# Arduino-DUE-V03A.net
KiCad netlist of a schematic drawn in EAGLE
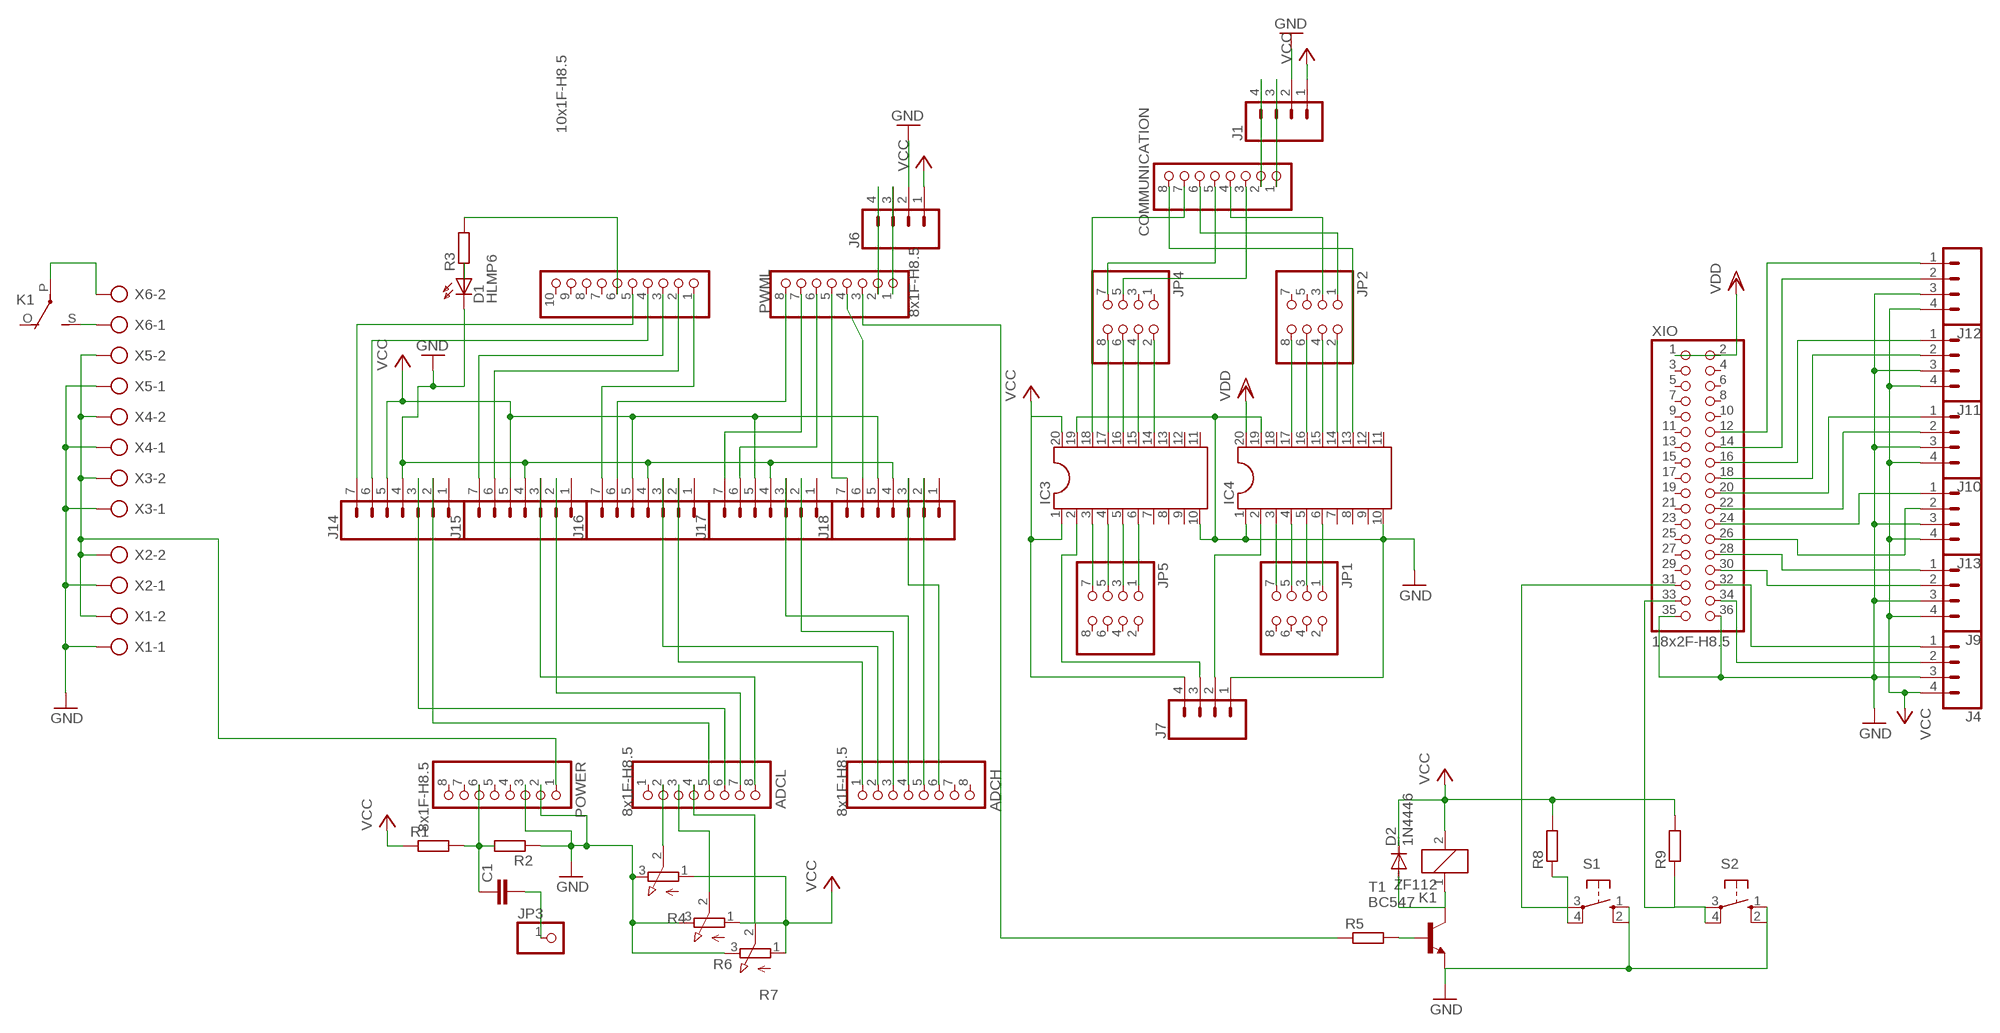
[diagram p0: schematic, sheet 1]

(export (version "E")
  (design (tool "Eeschema 10.0.6"))
  (components
    (comp (ref "ADCH")
      (value "8x1F-H8.5")
      (footprint "eagle-import:1X08")
      (libsource (lib "eagle-import") (part "PINHD-1X8"))
    )
    (comp (ref "ADCL")
      (value "8x1F-H8.5")
      (footprint "eagle-import:1X08")
      (libsource (lib "eagle-import") (part "PINHD-1X8"))
    )
    (comp (ref "C1")
      (value "C-EU025-025X050")
      (footprint "eagle-import:C025-025X050")
      (libsource (lib "eagle-import") (part "C-EU025-025X050"))
    )
    (comp (ref "COMMUNICATION")
      (value "8x1F-H8.5")
      (footprint "eagle-import:1X08")
      (libsource (lib "eagle-import") (part "PINHD-1X8"))
    )
    (comp (ref "D1")
      (value "HLMP6")
      (footprint "eagle-import:HLMP6")
      (fields (field (name "MF") "AGILENT TECHNOLOGIES") (field (name "MPN") "HLMP-6500"))
      (libsource (lib "eagle-import") (part "HLMP6"))
    )
    (comp (ref "D2")
      (value "1N4446")
      (footprint "eagle-import:DO35-10")
      (libsource (lib "eagle-import") (part "1N4446"))
    )
    (comp (ref "IC3")
      (value "DIL20S")
      (footprint "eagle-import:SOCKET-20")
      (libsource (lib "eagle-import") (part "DIL20S"))
    )
    (comp (ref "IC4")
      (value "DIL20S")
      (footprint "eagle-import:SOCKET-20")
      (libsource (lib "eagle-import") (part "DIL20S"))
    )
    (comp (ref "J1")
      (value "CONN_04LONGPADS")
      (footprint "eagle-import:1X04_LONGPADS")
      (libsource (lib "eagle-import") (part "CONN_04LONGPADS"))
    )
    (comp (ref "J4")
      (value "CONN_04LONGPADS")
      (footprint "eagle-import:1X04_LONGPADS")
      (libsource (lib "eagle-import") (part "CONN_04LONGPADS"))
    )
    (comp (ref "J6")
      (value "CONN_04LONGPADS")
      (footprint "eagle-import:1X04_LONGPADS")
      (libsource (lib "eagle-import") (part "CONN_04LONGPADS"))
    )
    (comp (ref "J7")
      (value "CONN_04LONGPADS")
      (footprint "eagle-import:1X04_LONGPADS")
      (libsource (lib "eagle-import") (part "CONN_04LONGPADS"))
    )
    (comp (ref "J9")
      (value "CONN_04LONGPADS")
      (footprint "eagle-import:1X04_LONGPADS")
      (libsource (lib "eagle-import") (part "CONN_04LONGPADS"))
    )
    (comp (ref "J10")
      (value "CONN_04LONGPADS")
      (footprint "eagle-import:1X04_LONGPADS")
      (libsource (lib "eagle-import") (part "CONN_04LONGPADS"))
    )
    (comp (ref "J11")
      (value "CONN_04LONGPADS")
      (footprint "eagle-import:1X04_LONGPADS")
      (libsource (lib "eagle-import") (part "CONN_04LONGPADS"))
    )
    (comp (ref "J12")
      (value "CONN_04LONGPADS")
      (footprint "eagle-import:1X04_LONGPADS")
      (libsource (lib "eagle-import") (part "CONN_04LONGPADS"))
    )
    (comp (ref "J13")
      (value "CONN_04LONGPADS")
      (footprint "eagle-import:1X04_LONGPADS")
      (libsource (lib "eagle-import") (part "CONN_04LONGPADS"))
    )
    (comp (ref "J14")
      (value "CONN_07LONGPADS")
      (footprint "eagle-import:1X07_LONGPADS")
      (libsource (lib "eagle-import") (part "CONN_07LONGPADS"))
    )
    (comp (ref "J15")
      (value "CONN_07LONGPADS")
      (footprint "eagle-import:1X07_LONGPADS")
      (libsource (lib "eagle-import") (part "CONN_07LONGPADS"))
    )
    (comp (ref "J16")
      (value "CONN_07LONGPADS")
      (footprint "eagle-import:1X07_LONGPADS")
      (libsource (lib "eagle-import") (part "CONN_07LONGPADS"))
    )
    (comp (ref "J17")
      (value "CONN_07LONGPADS")
      (footprint "eagle-import:1X07_LONGPADS")
      (libsource (lib "eagle-import") (part "CONN_07LONGPADS"))
    )
    (comp (ref "J18")
      (value "CONN_07LONGPADS")
      (footprint "eagle-import:1X07_LONGPADS")
      (libsource (lib "eagle-import") (part "CONN_07LONGPADS"))
    )
    (comp (ref "JP1")
      (value "PINHD-2X4")
      (footprint "eagle-import:2X04")
      (libsource (lib "eagle-import") (part "PINHD-2X4"))
    )
    (comp (ref "JP2")
      (value "PINHD-2X4")
      (footprint "eagle-import:2X04")
      (libsource (lib "eagle-import") (part "PINHD-2X4"))
    )
    (comp (ref "JP3")
      (value "PINHD-1X1")
      (footprint "eagle-import:1X01")
      (libsource (lib "eagle-import") (part "PINHD-1X1"))
    )
    (comp (ref "JP4")
      (value "PINHD-2X4")
      (footprint "eagle-import:2X04")
      (libsource (lib "eagle-import") (part "PINHD-2X4"))
    )
    (comp (ref "JP5")
      (value "PINHD-2X4")
      (footprint "eagle-import:2X04")
      (libsource (lib "eagle-import") (part "PINHD-2X4"))
    )
    (comp (ref "K1")
      (value "ZF112")
      (footprint "eagle-import:ZF112")
      (libsource (lib "eagle-import") (part "ZF112"))
    )
    (comp (ref "POWER")
      (value "8x1F-H8.5")
      (footprint "eagle-import:1X08")
      (libsource (lib "eagle-import") (part "PINHD-1X8"))
    )
    (comp (ref "PWMH")
      (value "10x1F-H8.5")
      (footprint "eagle-import:1X10")
      (libsource (lib "eagle-import") (part "PINHD-1X10"))
    )
    (comp (ref "PWML")
      (value "8x1F-H8.5")
      (footprint "eagle-import:1X08")
      (libsource (lib "eagle-import") (part "PINHD-1X8"))
    )
    (comp (ref "R1")
      (value "R-EU_0204/7")
      (footprint "eagle-import:0204_7")
      (libsource (lib "eagle-import") (part "R-EU_0204/7"))
    )
    (comp (ref "R2")
      (value "R-EU_0204/7")
      (footprint "eagle-import:0204_7")
      (libsource (lib "eagle-import") (part "R-EU_0204/7"))
    )
    (comp (ref "R3")
      (value "R-EU_0204/7")
      (footprint "eagle-import:0204_7")
      (libsource (lib "eagle-import") (part "R-EU_0204/7"))
    )
    (comp (ref "R4")
      (value "3RP/1610N")
      (footprint "eagle-import:3RP_1610N")
      (libsource (lib "eagle-import") (part "3RP/1610N"))
    )
    (comp (ref "R5")
      (value "R-EU_0204/7")
      (footprint "eagle-import:0204_7")
      (libsource (lib "eagle-import") (part "R-EU_0204/7"))
    )
    (comp (ref "R6")
      (value "3RP/1610N")
      (footprint "eagle-import:3RP_1610N")
      (libsource (lib "eagle-import") (part "3RP/1610N"))
    )
    (comp (ref "R7")
      (value "3RP/1610N")
      (footprint "eagle-import:3RP_1610N")
      (libsource (lib "eagle-import") (part "3RP/1610N"))
    )
    (comp (ref "R8")
      (value "R-EU_0204/7")
      (footprint "eagle-import:0204_7")
      (libsource (lib "eagle-import") (part "R-EU_0204/7"))
    )
    (comp (ref "R9")
      (value "R-EU_0204/7")
      (footprint "eagle-import:0204_7")
      (libsource (lib "eagle-import") (part "R-EU_0204/7"))
    )
    (comp (ref "S1")
      (value "10-XX")
      (footprint "eagle-import:B3F-10XX")
      (fields (field (name "MPN") "B3F-1000"))
      (libsource (lib "eagle-import") (part "10-XX"))
    )
    (comp (ref "S2")
      (value "10-XX")
      (footprint "eagle-import:B3F-10XX")
      (fields (field (name "MPN") "B3F-1000"))
      (libsource (lib "eagle-import") (part "10-XX"))
    )
    (comp (ref "T1")
      (value "BC547")
      (footprint "eagle-import:TO92")
      (libsource (lib "eagle-import") (part "BC547"))
    )
    (comp (ref "X1")
      (value "AK500/2")
      (footprint "eagle-import:AK500_2")
      (libsource (lib "eagle-import") (part "AK500/2"))
    )
    (comp (ref "X2")
      (value "AK500/2")
      (footprint "eagle-import:AK500_2")
      (libsource (lib "eagle-import") (part "AK500/2"))
    )
    (comp (ref "X3")
      (value "AK500/2")
      (footprint "eagle-import:AK500_2")
      (libsource (lib "eagle-import") (part "AK500/2"))
    )
    (comp (ref "X4")
      (value "AK500/2")
      (footprint "eagle-import:AK500_2")
      (libsource (lib "eagle-import") (part "AK500/2"))
    )
    (comp (ref "X5")
      (value "AK500/2")
      (footprint "eagle-import:AK500_2")
      (libsource (lib "eagle-import") (part "AK500/2"))
    )
    (comp (ref "X6")
      (value "AK500/2")
      (footprint "eagle-import:AK500_2")
      (libsource (lib "eagle-import") (part "AK500/2"))
    )
    (comp (ref "XIO")
      (value "18x2F-H8.5")
      (footprint "eagle-import:2X18")
      (libsource (lib "eagle-import") (part "PINHD-2X18"))
    )
  )
  (nets
    (net (code "1") (name "GND") (class "Default")
      (node (ref "D1") (pin "K") (pinfunction "K_K") (pintype "passive"))
      (node (ref "IC3") (pin "10") (pinfunction "10_10") (pintype "passive"))
      (node (ref "IC3") (pin "19") (pinfunction "19_19") (pintype "passive"))
      (node (ref "IC4") (pin "1") (pinfunction "1_1") (pintype "passive"))
      (node (ref "IC4") (pin "10") (pinfunction "10_10") (pintype "passive"))
      (node (ref "IC4") (pin "19") (pinfunction "19_19") (pintype "passive"))
      (node (ref "J1") (pin "2") (pinfunction "2_2") (pintype "passive"))
      (node (ref "J10") (pin "3") (pinfunction "3_3") (pintype "passive"))
      (node (ref "J11") (pin "3") (pinfunction "3_3") (pintype "passive"))
      (node (ref "J12") (pin "3") (pinfunction "3_3") (pintype "passive"))
      (node (ref "J13") (pin "1") (pinfunction "1_1") (pintype "passive"))
      (node (ref "J13") (pin "3") (pinfunction "3_3") (pintype "passive"))
      (node (ref "J14") (pin "4") (pinfunction "4_4") (pintype "passive"))
      (node (ref "J15") (pin "4") (pinfunction "4_4") (pintype "passive"))
      (node (ref "J16") (pin "4") (pinfunction "4_4") (pintype "passive"))
      (node (ref "J17") (pin "4") (pinfunction "4_4") (pintype "passive"))
      (node (ref "J18") (pin "4") (pinfunction "4_4") (pintype "passive"))
      (node (ref "J4") (pin "3") (pinfunction "3_3") (pintype "passive"))
      (node (ref "J6") (pin "2") (pinfunction "2_2") (pintype "passive"))
      (node (ref "J7") (pin "1") (pinfunction "1_1") (pintype "passive"))
      (node (ref "J9") (pin "3") (pinfunction "3_3") (pintype "passive"))
      (node (ref "POWER") (pin "2") (pinfunction "2_2") (pintype "passive"))
      (node (ref "POWER") (pin "3") (pinfunction "3_3") (pintype "passive"))
      (node (ref "R2") (pin "1") (pinfunction "1_1") (pintype "passive"))
      (node (ref "R4") (pin "3") (pinfunction "E_3") (pintype "passive"))
      (node (ref "R6") (pin "3") (pinfunction "E_3") (pintype "passive"))
      (node (ref "R7") (pin "3") (pinfunction "E_3") (pintype "passive"))
      (node (ref "S1") (pin "1") (pinfunction "S_1") (pintype "passive"))
      (node (ref "S1") (pin "2") (pinfunction "S1_2") (pintype "passive"))
      (node (ref "S2") (pin "1") (pinfunction "S_1") (pintype "passive"))
      (node (ref "S2") (pin "2") (pinfunction "S1_2") (pintype "passive"))
      (node (ref "T1") (pin "1") (pinfunction "E_1") (pintype "passive"))
      (node (ref "X1") (pin "1") (pinfunction "KL_1") (pintype "passive"))
      (node (ref "X2") (pin "1") (pinfunction "KL_1") (pintype "passive"))
      (node (ref "X3") (pin "1") (pinfunction "KL_1") (pintype "passive"))
      (node (ref "X4") (pin "1") (pinfunction "KL_1") (pintype "passive"))
      (node (ref "X5") (pin "1") (pinfunction "KL_1") (pintype "passive"))
      (node (ref "XIO") (pin "24") (pinfunction "24_24") (pintype "passive"))
      (node (ref "XIO") (pin "35") (pinfunction "35_35") (pintype "passive"))
      (node (ref "XIO") (pin "36") (pinfunction "36_36") (pintype "passive"))
    )
    (net (code "2") (name "Net-(ADCH-Pad1)") (class "Default")
      (node (ref "ADCH") (pin "1") (pinfunction "1_1") (pintype "passive"))
      (node (ref "J16") (pin "2") (pinfunction "2_2") (pintype "passive"))
    )
    (net (code "3") (name "Net-(ADCH-Pad2)") (class "Default")
      (node (ref "ADCH") (pin "2") (pinfunction "2_2") (pintype "passive"))
      (node (ref "J16") (pin "3") (pinfunction "3_3") (pintype "passive"))
    )
    (net (code "4") (name "Net-(ADCH-Pad3)") (class "Default")
      (node (ref "ADCH") (pin "3") (pinfunction "3_3") (pintype "passive"))
      (node (ref "J17") (pin "2") (pinfunction "2_2") (pintype "passive"))
    )
    (net (code "5") (name "Net-(ADCH-Pad4)") (class "Default")
      (node (ref "ADCH") (pin "4") (pinfunction "4_4") (pintype "passive"))
      (node (ref "J17") (pin "3") (pinfunction "3_3") (pintype "passive"))
    )
    (net (code "6") (name "Net-(ADCH-Pad5)") (class "Default")
      (node (ref "ADCH") (pin "5") (pinfunction "5_5") (pintype "passive"))
      (node (ref "J18") (pin "2") (pinfunction "2_2") (pintype "passive"))
    )
    (net (code "7") (name "Net-(ADCH-Pad6)") (class "Default")
      (node (ref "ADCH") (pin "6") (pinfunction "6_6") (pintype "passive"))
      (node (ref "J18") (pin "3") (pinfunction "3_3") (pintype "passive"))
    )
    (net (code "8") (name "Net-(ADCL-Pad5)") (class "Default")
      (node (ref "ADCL") (pin "5") (pinfunction "5_5") (pintype "passive"))
      (node (ref "J14") (pin "2") (pinfunction "2_2") (pintype "passive"))
    )
    (net (code "9") (name "Net-(ADCL-Pad6)") (class "Default")
      (node (ref "ADCL") (pin "6") (pinfunction "6_6") (pintype "passive"))
      (node (ref "J14") (pin "3") (pinfunction "3_3") (pintype "passive"))
    )
    (net (code "10") (name "Net-(ADCL-Pad7)") (class "Default")
      (node (ref "ADCL") (pin "7") (pinfunction "7_7") (pintype "passive"))
      (node (ref "J15") (pin "2") (pinfunction "2_2") (pintype "passive"))
    )
    (net (code "11") (name "Net-(ADCL-Pad8)") (class "Default")
      (node (ref "ADCL") (pin "8") (pinfunction "8_8") (pintype "passive"))
      (node (ref "J15") (pin "3") (pinfunction "3_3") (pintype "passive"))
    )
    (net (code "12") (name "Net-(C1-Pad1)") (class "Default")
      (node (ref "C1") (pin "1") (pinfunction "1_1") (pintype "passive"))
      (node (ref "POWER") (pin "6") (pinfunction "6_6") (pintype "passive"))
      (node (ref "R1") (pin "2") (pinfunction "2_2") (pintype "passive"))
      (node (ref "R2") (pin "2") (pinfunction "2_2") (pintype "passive"))
    )
    (net (code "13") (name "Net-(C1-Pad2)") (class "Default")
      (node (ref "C1") (pin "2") (pinfunction "2_2") (pintype "passive"))
      (node (ref "JP3") (pin "1") (pinfunction "1_1") (pintype "passive"))
    )
    (net (code "14") (name "Net-(COMMUNICATION-Pad1)") (class "Default")
      (node (ref "COMMUNICATION") (pin "1") (pinfunction "1_1") (pintype "passive"))
      (node (ref "J1") (pin "3") (pinfunction "3_3") (pintype "passive"))
    )
    (net (code "15") (name "Net-(COMMUNICATION-Pad2)") (class "Default")
      (node (ref "COMMUNICATION") (pin "2") (pinfunction "2_2") (pintype "passive"))
      (node (ref "J1") (pin "4") (pinfunction "4_4") (pintype "passive"))
    )
    (net (code "16") (name "Net-(COMMUNICATION-Pad3)") (class "Default")
      (node (ref "COMMUNICATION") (pin "3") (pinfunction "3_3") (pintype "passive"))
      (node (ref "JP4") (pin "5") (pinfunction "5_5") (pintype "passive"))
    )
    (net (code "17") (name "Net-(COMMUNICATION-Pad4)") (class "Default")
      (node (ref "COMMUNICATION") (pin "4") (pinfunction "4_4") (pintype "passive"))
      (node (ref "JP2") (pin "3") (pinfunction "3_3") (pintype "passive"))
    )
    (net (code "18") (name "Net-(COMMUNICATION-Pad5)") (class "Default")
      (node (ref "COMMUNICATION") (pin "5") (pinfunction "5_5") (pintype "passive"))
      (node (ref "JP4") (pin "7") (pinfunction "7_7") (pintype "passive"))
    )
    (net (code "19") (name "Net-(COMMUNICATION-Pad6)") (class "Default")
      (node (ref "COMMUNICATION") (pin "6") (pinfunction "6_6") (pintype "passive"))
      (node (ref "JP2") (pin "1") (pinfunction "1_1") (pintype "passive"))
    )
    (net (code "20") (name "Net-(COMMUNICATION-Pad7)") (class "Default")
      (node (ref "COMMUNICATION") (pin "7") (pinfunction "7_7") (pintype "passive"))
      (node (ref "IC3") (pin "18") (pinfunction "18_18") (pintype "passive"))
    )
    (net (code "21") (name "Net-(COMMUNICATION-Pad8)") (class "Default")
      (node (ref "COMMUNICATION") (pin "8") (pinfunction "8_8") (pintype "passive"))
      (node (ref "IC4") (pin "13") (pinfunction "13_13") (pintype "passive"))
    )
    (net (code "22") (name "Net-(D1-PadA)") (class "Default")
      (node (ref "D1") (pin "A") (pinfunction "A_A") (pintype "passive"))
      (node (ref "R3") (pin "1") (pinfunction "1_1") (pintype "passive"))
    )
    (net (code "23") (name "Net-(IC3-Pad2)") (class "Default")
      (node (ref "IC3") (pin "2") (pinfunction "2_2") (pintype "passive"))
      (node (ref "J7") (pin "3") (pinfunction "3_3") (pintype "passive"))
    )
    (net (code "24") (name "Net-(IC3-Pad3)") (class "Default")
      (node (ref "IC3") (pin "3") (pinfunction "3_3") (pintype "passive"))
      (node (ref "JP5") (pin "7") (pinfunction "7_7") (pintype "passive"))
    )
    (net (code "25") (name "Net-(IC3-Pad4)") (class "Default")
      (node (ref "IC3") (pin "4") (pinfunction "4_4") (pintype "passive"))
      (node (ref "JP5") (pin "5") (pinfunction "5_5") (pintype "passive"))
    )
    (net (code "26") (name "Net-(IC3-Pad5)") (class "Default")
      (node (ref "IC3") (pin "5") (pinfunction "5_5") (pintype "passive"))
      (node (ref "JP5") (pin "3") (pinfunction "3_3") (pintype "passive"))
    )
    (net (code "27") (name "Net-(IC3-Pad6)") (class "Default")
      (node (ref "IC3") (pin "6") (pinfunction "6_6") (pintype "passive"))
      (node (ref "JP5") (pin "1") (pinfunction "1_1") (pintype "passive"))
    )
    (net (code "28") (name "Net-(IC3-Pad14)") (class "Default")
      (node (ref "IC3") (pin "14") (pinfunction "14_14") (pintype "passive"))
      (node (ref "JP4") (pin "2") (pinfunction "2_2") (pintype "passive"))
    )
    (net (code "29") (name "Net-(IC3-Pad15)") (class "Default")
      (node (ref "IC3") (pin "15") (pinfunction "15_15") (pintype "passive"))
      (node (ref "JP4") (pin "4") (pinfunction "4_4") (pintype "passive"))
    )
    (net (code "30") (name "Net-(IC3-Pad16)") (class "Default")
      (node (ref "IC3") (pin "16") (pinfunction "16_16") (pintype "passive"))
      (node (ref "JP4") (pin "6") (pinfunction "6_6") (pintype "passive"))
    )
    (net (code "31") (name "Net-(IC3-Pad17)") (class "Default")
      (node (ref "IC3") (pin "17") (pinfunction "17_17") (pintype "passive"))
      (node (ref "JP4") (pin "8") (pinfunction "8_8") (pintype "passive"))
    )
    (net (code "32") (name "Net-(IC4-Pad2)") (class "Default")
      (node (ref "IC4") (pin "2") (pinfunction "2_2") (pintype "passive"))
      (node (ref "J7") (pin "2") (pinfunction "2_2") (pintype "passive"))
    )
    (net (code "33") (name "Net-(IC4-Pad3)") (class "Default")
      (node (ref "IC4") (pin "3") (pinfunction "3_3") (pintype "passive"))
      (node (ref "JP1") (pin "7") (pinfunction "7_7") (pintype "passive"))
    )
    (net (code "34") (name "Net-(IC4-Pad4)") (class "Default")
      (node (ref "IC4") (pin "4") (pinfunction "4_4") (pintype "passive"))
      (node (ref "JP1") (pin "5") (pinfunction "5_5") (pintype "passive"))
    )
    (net (code "35") (name "Net-(IC4-Pad5)") (class "Default")
      (node (ref "IC4") (pin "5") (pinfunction "5_5") (pintype "passive"))
      (node (ref "JP1") (pin "3") (pinfunction "3_3") (pintype "passive"))
    )
    (net (code "36") (name "Net-(IC4-Pad6)") (class "Default")
      (node (ref "IC4") (pin "6") (pinfunction "6_6") (pintype "passive"))
      (node (ref "JP1") (pin "1") (pinfunction "1_1") (pintype "passive"))
    )
    (net (code "37") (name "Net-(IC4-Pad14)") (class "Default")
      (node (ref "IC4") (pin "14") (pinfunction "14_14") (pintype "passive"))
      (node (ref "JP2") (pin "2") (pinfunction "2_2") (pintype "passive"))
    )
    (net (code "38") (name "Net-(IC4-Pad15)") (class "Default")
      (node (ref "IC4") (pin "15") (pinfunction "15_15") (pintype "passive"))
      (node (ref "JP2") (pin "4") (pinfunction "4_4") (pintype "passive"))
    )
    (net (code "39") (name "Net-(IC4-Pad16)") (class "Default")
      (node (ref "IC4") (pin "16") (pinfunction "16_16") (pintype "passive"))
      (node (ref "JP2") (pin "6") (pinfunction "6_6") (pintype "passive"))
    )
    (net (code "40") (name "Net-(IC4-Pad17)") (class "Default")
      (node (ref "IC4") (pin "17") (pinfunction "17_17") (pintype "passive"))
      (node (ref "JP2") (pin "8") (pinfunction "8_8") (pintype "passive"))
    )
    (net (code "41") (name "Net-(J4-Pad1)") (class "Default")
      (node (ref "J4") (pin "1") (pinfunction "1_1") (pintype "passive"))
      (node (ref "XIO") (pin "32") (pinfunction "32_32") (pintype "passive"))
    )
    (net (code "42") (name "Net-(J4-Pad2)") (class "Default")
      (node (ref "J4") (pin "2") (pinfunction "2_2") (pintype "passive"))
      (node (ref "XIO") (pin "34") (pinfunction "34_34") (pintype "passive"))
    )
    (net (code "43") (name "Net-(J6-Pad3)") (class "Default")
      (node (ref "J6") (pin "3") (pinfunction "3_3") (pintype "passive"))
      (node (ref "PWML") (pin "1") (pinfunction "1_1") (pintype "passive"))
    )
    (net (code "44") (name "Net-(J6-Pad4)") (class "Default")
      (node (ref "J6") (pin "4") (pinfunction "4_4") (pintype "passive"))
      (node (ref "PWML") (pin "2") (pinfunction "2_2") (pintype "passive"))
    )
    (net (code "45") (name "Net-(J9-Pad1)") (class "Default")
      (node (ref "J9") (pin "1") (pinfunction "1_1") (pintype "passive"))
      (node (ref "XIO") (pin "28") (pinfunction "28_28") (pintype "passive"))
    )
    (net (code "46") (name "Net-(J9-Pad2)") (class "Default")
      (node (ref "J9") (pin "2") (pinfunction "2_2") (pintype "passive"))
      (node (ref "XIO") (pin "30") (pinfunction "30_30") (pintype "passive"))
    )
    (net (code "47") (name "Net-(J10-Pad1)") (class "Default")
      (node (ref "J10") (pin "1") (pinfunction "1_1") (pintype "passive"))
      (node (ref "XIO") (pin "20") (pinfunction "20_20") (pintype "passive"))
    )
    (net (code "48") (name "Net-(J10-Pad2)") (class "Default")
      (node (ref "J10") (pin "2") (pinfunction "2_2") (pintype "passive"))
      (node (ref "XIO") (pin "22") (pinfunction "22_22") (pintype "passive"))
    )
    (net (code "49") (name "Net-(J11-Pad1)") (class "Default")
      (node (ref "J11") (pin "1") (pinfunction "1_1") (pintype "passive"))
      (node (ref "XIO") (pin "16") (pinfunction "16_16") (pintype "passive"))
    )
    (net (code "50") (name "Net-(J11-Pad2)") (class "Default")
      (node (ref "J11") (pin "2") (pinfunction "2_2") (pintype "passive"))
      (node (ref "XIO") (pin "18") (pinfunction "18_18") (pintype "passive"))
    )
    (net (code "51") (name "Net-(J12-Pad1)") (class "Default")
      (node (ref "J12") (pin "1") (pinfunction "1_1") (pintype "passive"))
      (node (ref "XIO") (pin "12") (pinfunction "12_12") (pintype "passive"))
    )
    (net (code "52") (name "Net-(J12-Pad2)") (class "Default")
      (node (ref "J12") (pin "2") (pinfunction "2_2") (pintype "passive"))
      (node (ref "XIO") (pin "14") (pinfunction "14_14") (pintype "passive"))
    )
    (net (code "53") (name "Net-(J13-Pad2)") (class "Default")
      (node (ref "J13") (pin "2") (pinfunction "2_2") (pintype "passive"))
      (node (ref "XIO") (pin "26") (pinfunction "26_26") (pintype "passive"))
    )
    (net (code "54") (name "Net-(J14-Pad6)") (class "Default")
      (node (ref "J14") (pin "6") (pinfunction "6_6") (pintype "passive"))
      (node (ref "PWMH") (pin "4") (pinfunction "4_4") (pintype "passive"))
    )
    (net (code "55") (name "Net-(J14-Pad7)") (class "Default")
      (node (ref "J14") (pin "7") (pinfunction "7_7") (pintype "passive"))
      (node (ref "PWMH") (pin "5") (pinfunction "5_5") (pintype "passive"))
    )
    (net (code "56") (name "Net-(J15-Pad6)") (class "Default")
      (node (ref "J15") (pin "6") (pinfunction "6_6") (pintype "passive"))
      (node (ref "PWMH") (pin "2") (pinfunction "2_2") (pintype "passive"))
    )
    (net (code "57") (name "Net-(J15-Pad7)") (class "Default")
      (node (ref "J15") (pin "7") (pinfunction "7_7") (pintype "passive"))
      (node (ref "PWMH") (pin "3") (pinfunction "3_3") (pintype "passive"))
    )
    (net (code "58") (name "Net-(J16-Pad6)") (class "Default")
      (node (ref "J16") (pin "6") (pinfunction "6_6") (pintype "passive"))
      (node (ref "PWML") (pin "8") (pinfunction "8_8") (pintype "passive"))
    )
    (net (code "59") (name "Net-(J16-Pad7)") (class "Default")
      (node (ref "J16") (pin "7") (pinfunction "7_7") (pintype "passive"))
      (node (ref "PWMH") (pin "1") (pinfunction "1_1") (pintype "passive"))
    )
    (net (code "60") (name "Net-(J17-Pad6)") (class "Default")
      (node (ref "J17") (pin "6") (pinfunction "6_6") (pintype "passive"))
      (node (ref "PWML") (pin "6") (pinfunction "6_6") (pintype "passive"))
    )
    (net (code "61") (name "Net-(J17-Pad7)") (class "Default")
      (node (ref "J17") (pin "7") (pinfunction "7_7") (pintype "passive"))
      (node (ref "PWML") (pin "7") (pinfunction "7_7") (pintype "passive"))
    )
    (net (code "62") (name "Net-(J18-Pad6)") (class "Default")
      (node (ref "J18") (pin "6") (pinfunction "6_6") (pintype "passive"))
      (node (ref "PWML") (pin "4") (pinfunction "4_4") (pintype "passive"))
    )
    (net (code "63") (name "Net-(J18-Pad7)") (class "Default")
      (node (ref "J18") (pin "7") (pinfunction "7_7") (pintype "passive"))
      (node (ref "PWML") (pin "5") (pinfunction "5_5") (pintype "passive"))
    )
    (net (code "64") (name "Net-(PWMH-Pad6)") (class "Default")
      (node (ref "PWMH") (pin "6") (pinfunction "6_6") (pintype "passive"))
      (node (ref "R3") (pin "2") (pinfunction "2_2") (pintype "passive"))
    )
    (net (code "65") (name "Net-(PWML-Pad3)") (class "Default")
      (node (ref "PWML") (pin "3") (pinfunction "3_3") (pintype "passive"))
      (node (ref "R5") (pin "1") (pinfunction "1_1") (pintype "passive"))
    )
    (net (code "66") (name "Net-(R4-S)") (class "Default")
      (node (ref "ADCL") (pin "2") (pinfunction "2_2") (pintype "passive"))
      (node (ref "R4") (pin "2") (pinfunction "S_2") (pintype "passive"))
    )
    (net (code "67") (name "Net-(R6-S)") (class "Default")
      (node (ref "ADCL") (pin "3") (pinfunction "3_3") (pintype "passive"))
      (node (ref "R6") (pin "2") (pinfunction "S_2") (pintype "passive"))
    )
    (net (code "68") (name "Net-(R7-S)") (class "Default")
      (node (ref "ADCL") (pin "4") (pinfunction "4_4") (pintype "passive"))
      (node (ref "R7") (pin "2") (pinfunction "S_2") (pintype "passive"))
    )
    (net (code "69") (name "Net-(S1-P)") (class "Default")
      (node (ref "R8") (pin "1") (pinfunction "1_1") (pintype "passive"))
      (node (ref "S1") (pin "3") (pinfunction "P_3") (pintype "passive"))
      (node (ref "S1") (pin "4") (pinfunction "P1_4") (pintype "passive"))
      (node (ref "XIO") (pin "31") (pinfunction "31_31") (pintype "passive"))
    )
    (net (code "70") (name "Net-(S2-P)") (class "Default")
      (node (ref "R9") (pin "1") (pinfunction "1_1") (pintype "passive"))
      (node (ref "S2") (pin "3") (pinfunction "P_3") (pintype "passive"))
      (node (ref "S2") (pin "4") (pinfunction "P1_4") (pintype "passive"))
      (node (ref "XIO") (pin "33") (pinfunction "33_33") (pintype "passive"))
    )
    (net (code "71") (name "Net-(T1-B)") (class "Default")
      (node (ref "R5") (pin "2") (pinfunction "2_2") (pintype "passive"))
      (node (ref "T1") (pin "2") (pinfunction "B_2") (pintype "passive"))
    )
    (net (code "72") (name "Net-(T1-C)") (class "Default")
      (node (ref "D2") (pin "A") (pinfunction "A_A") (pintype "passive"))
      (node (ref "K1") (pin "1") (pinfunction "1_1") (pintype "passive"))
      (node (ref "T1") (pin "3") (pinfunction "C_3") (pintype "passive"))
    )
    (net (code "73") (name "Net-(X1B-KL)") (class "Default")
      (node (ref "POWER") (pin "1") (pinfunction "1_1") (pintype "passive"))
      (node (ref "X1") (pin "2") (pinfunction "KL_2") (pintype "passive"))
      (node (ref "X2") (pin "2") (pinfunction "KL_2") (pintype "passive"))
      (node (ref "X3") (pin "2") (pinfunction "KL_2") (pintype "passive"))
      (node (ref "X4") (pin "2") (pinfunction "KL_2") (pintype "passive"))
      (node (ref "X5") (pin "2") (pinfunction "KL_2") (pintype "passive"))
    )
    (net (code "74") (name "Net-(X6A-KL)") (class "Default")
      (node (ref "K1") (pin "S") (pinfunction "S_S") (pintype "passive"))
      (node (ref "X6") (pin "1") (pinfunction "KL_1") (pintype "passive"))
    )
    (net (code "75") (name "Net-(X6B-KL)") (class "Default")
      (node (ref "K1") (pin "P") (pinfunction "P_P") (pintype "passive"))
      (node (ref "X6") (pin "2") (pinfunction "KL_2") (pintype "passive"))
    )
    (net (code "76") (name "VCC") (class "Default")
      (node (ref "D2") (pin "C") (pinfunction "C_C") (pintype "passive"))
      (node (ref "IC3") (pin "1") (pinfunction "1_1") (pintype "passive"))
      (node (ref "IC3") (pin "20") (pinfunction "20_20") (pintype "passive"))
      (node (ref "J1") (pin "1") (pinfunction "1_1") (pintype "passive"))
      (node (ref "J10") (pin "4") (pinfunction "4_4") (pintype "passive"))
      (node (ref "J11") (pin "4") (pinfunction "4_4") (pintype "passive"))
      (node (ref "J12") (pin "4") (pinfunction "4_4") (pintype "passive"))
      (node (ref "J13") (pin "4") (pinfunction "4_4") (pintype "passive"))
      (node (ref "J14") (pin "5") (pinfunction "5_5") (pintype "passive"))
      (node (ref "J15") (pin "5") (pinfunction "5_5") (pintype "passive"))
      (node (ref "J16") (pin "5") (pinfunction "5_5") (pintype "passive"))
      (node (ref "J17") (pin "5") (pinfunction "5_5") (pintype "passive"))
      (node (ref "J18") (pin "5") (pinfunction "5_5") (pintype "passive"))
      (node (ref "J4") (pin "4") (pinfunction "4_4") (pintype "passive"))
      (node (ref "J6") (pin "1") (pinfunction "1_1") (pintype "passive"))
      (node (ref "J7") (pin "4") (pinfunction "4_4") (pintype "passive"))
      (node (ref "J9") (pin "4") (pinfunction "4_4") (pintype "passive"))
      (node (ref "K1") (pin "2") (pinfunction "2_2") (pintype "passive"))
      (node (ref "R1") (pin "1") (pinfunction "1_1") (pintype "passive"))
      (node (ref "R4") (pin "1") (pinfunction "A_1") (pintype "passive"))
      (node (ref "R6") (pin "1") (pinfunction "A_1") (pintype "passive"))
      (node (ref "R7") (pin "1") (pinfunction "A_1") (pintype "passive"))
      (node (ref "R8") (pin "2") (pinfunction "2_2") (pintype "passive"))
      (node (ref "R9") (pin "2") (pinfunction "2_2") (pintype "passive"))
    )
    (net (code "77") (name "VDD") (class "Default")
      (node (ref "IC4") (pin "20") (pinfunction "20_20") (pintype "passive"))
      (node (ref "XIO") (pin "1") (pinfunction "1_1") (pintype "passive"))
      (node (ref "XIO") (pin "2") (pinfunction "2_2") (pintype "passive"))
    )
    (net (code "78") (name "unconnected-(ADCH-Pad7)") (class "Default")
      (node (ref "ADCH") (pin "7") (pinfunction "7_7") (pintype "passive"))
    )
    (net (code "79") (name "unconnected-(ADCH-Pad8)") (class "Default")
      (node (ref "ADCH") (pin "8") (pinfunction "8_8") (pintype "passive"))
    )
    (net (code "80") (name "unconnected-(ADCL-Pad1)") (class "Default")
      (node (ref "ADCL") (pin "1") (pinfunction "1_1") (pintype "passive"))
    )
    (net (code "81") (name "unconnected-(IC3-Pad7)") (class "Default")
      (node (ref "IC3") (pin "7") (pinfunction "7_7") (pintype "passive"))
    )
    (net (code "82") (name "unconnected-(IC3-Pad8)") (class "Default")
      (node (ref "IC3") (pin "8") (pinfunction "8_8") (pintype "passive"))
    )
    (net (code "83") (name "unconnected-(IC3-Pad9)") (class "Default")
      (node (ref "IC3") (pin "9") (pinfunction "9_9") (pintype "passive"))
    )
    (net (code "84") (name "unconnected-(IC3-Pad11)") (class "Default")
      (node (ref "IC3") (pin "11") (pinfunction "11_11") (pintype "passive"))
    )
    (net (code "85") (name "unconnected-(IC3-Pad12)") (class "Default")
      (node (ref "IC3") (pin "12") (pinfunction "12_12") (pintype "passive"))
    )
    (net (code "86") (name "unconnected-(IC3-Pad13)") (class "Default")
      (node (ref "IC3") (pin "13") (pinfunction "13_13") (pintype "passive"))
    )
    (net (code "87") (name "unconnected-(IC4-Pad7)") (class "Default")
      (node (ref "IC4") (pin "7") (pinfunction "7_7") (pintype "passive"))
    )
    (net (code "88") (name "unconnected-(IC4-Pad8)") (class "Default")
      (node (ref "IC4") (pin "8") (pinfunction "8_8") (pintype "passive"))
    )
    (net (code "89") (name "unconnected-(IC4-Pad9)") (class "Default")
      (node (ref "IC4") (pin "9") (pinfunction "9_9") (pintype "passive"))
    )
    (net (code "90") (name "unconnected-(IC4-Pad11)") (class "Default")
      (node (ref "IC4") (pin "11") (pinfunction "11_11") (pintype "passive"))
    )
    (net (code "91") (name "unconnected-(IC4-Pad12)") (class "Default")
      (node (ref "IC4") (pin "12") (pinfunction "12_12") (pintype "passive"))
    )
    (net (code "92") (name "unconnected-(IC4-Pad18)") (class "Default")
      (node (ref "IC4") (pin "18") (pinfunction "18_18") (pintype "passive"))
    )
    (net (code "93") (name "unconnected-(J14-Pad1)") (class "Default")
      (node (ref "J14") (pin "1") (pinfunction "1_1") (pintype "passive"))
    )
    (net (code "94") (name "unconnected-(J15-Pad1)") (class "Default")
      (node (ref "J15") (pin "1") (pinfunction "1_1") (pintype "passive"))
    )
    (net (code "95") (name "unconnected-(J16-Pad1)") (class "Default")
      (node (ref "J16") (pin "1") (pinfunction "1_1") (pintype "passive"))
    )
    (net (code "96") (name "unconnected-(J17-Pad1)") (class "Default")
      (node (ref "J17") (pin "1") (pinfunction "1_1") (pintype "passive"))
    )
    (net (code "97") (name "unconnected-(J18-Pad1)") (class "Default")
      (node (ref "J18") (pin "1") (pinfunction "1_1") (pintype "passive"))
    )
    (net (code "98") (name "unconnected-(JP1-Pad2)") (class "Default")
      (node (ref "JP1") (pin "2") (pinfunction "2_2") (pintype "passive"))
    )
    (net (code "99") (name "unconnected-(JP1-Pad4)") (class "Default")
      (node (ref "JP1") (pin "4") (pinfunction "4_4") (pintype "passive"))
    )
    (net (code "100") (name "unconnected-(JP1-Pad6)") (class "Default")
      (node (ref "JP1") (pin "6") (pinfunction "6_6") (pintype "passive"))
    )
    (net (code "101") (name "unconnected-(JP1-Pad8)") (class "Default")
      (node (ref "JP1") (pin "8") (pinfunction "8_8") (pintype "passive"))
    )
    (net (code "102") (name "unconnected-(JP2-Pad5)") (class "Default")
      (node (ref "JP2") (pin "5") (pinfunction "5_5") (pintype "passive"))
    )
    (net (code "103") (name "unconnected-(JP2-Pad7)") (class "Default")
      (node (ref "JP2") (pin "7") (pinfunction "7_7") (pintype "passive"))
    )
    (net (code "104") (name "unconnected-(JP4-Pad1)") (class "Default")
      (node (ref "JP4") (pin "1") (pinfunction "1_1") (pintype "passive"))
    )
    (net (code "105") (name "unconnected-(JP4-Pad3)") (class "Default")
      (node (ref "JP4") (pin "3") (pinfunction "3_3") (pintype "passive"))
    )
    (net (code "106") (name "unconnected-(JP5-Pad2)") (class "Default")
      (node (ref "JP5") (pin "2") (pinfunction "2_2") (pintype "passive"))
    )
    (net (code "107") (name "unconnected-(JP5-Pad4)") (class "Default")
      (node (ref "JP5") (pin "4") (pinfunction "4_4") (pintype "passive"))
    )
    (net (code "108") (name "unconnected-(JP5-Pad6)") (class "Default")
      (node (ref "JP5") (pin "6") (pinfunction "6_6") (pintype "passive"))
    )
    (net (code "109") (name "unconnected-(JP5-Pad8)") (class "Default")
      (node (ref "JP5") (pin "8") (pinfunction "8_8") (pintype "passive"))
    )
    (net (code "110") (name "unconnected-(K1-PadO)") (class "Default")
      (node (ref "K1") (pin "O") (pinfunction "O_O") (pintype "passive"))
    )
    (net (code "111") (name "unconnected-(POWER-Pad4)") (class "Default")
      (node (ref "POWER") (pin "4") (pinfunction "4_4") (pintype "passive"))
    )
    (net (code "112") (name "unconnected-(POWER-Pad5)") (class "Default")
      (node (ref "POWER") (pin "5") (pinfunction "5_5") (pintype "passive"))
    )
    (net (code "113") (name "unconnected-(POWER-Pad7)") (class "Default")
      (node (ref "POWER") (pin "7") (pinfunction "7_7") (pintype "passive"))
    )
    (net (code "114") (name "unconnected-(POWER-Pad8)") (class "Default")
      (node (ref "POWER") (pin "8") (pinfunction "8_8") (pintype "passive"))
    )
    (net (code "115") (name "unconnected-(PWMH-Pad7)") (class "Default")
      (node (ref "PWMH") (pin "7") (pinfunction "7_7") (pintype "passive"))
    )
    (net (code "116") (name "unconnected-(PWMH-Pad8)") (class "Default")
      (node (ref "PWMH") (pin "8") (pinfunction "8_8") (pintype "passive"))
    )
    (net (code "117") (name "unconnected-(PWMH-Pad9)") (class "Default")
      (node (ref "PWMH") (pin "9") (pinfunction "9_9") (pintype "passive"))
    )
    (net (code "118") (name "unconnected-(PWMH-Pad10)") (class "Default")
      (node (ref "PWMH") (pin "10") (pinfunction "10_10") (pintype "passive"))
    )
    (net (code "119") (name "unconnected-(XIO-Pad3)") (class "Default")
      (node (ref "XIO") (pin "3") (pinfunction "3_3") (pintype "passive"))
    )
    (net (code "120") (name "unconnected-(XIO-Pad4)") (class "Default")
      (node (ref "XIO") (pin "4") (pinfunction "4_4") (pintype "passive"))
    )
    (net (code "121") (name "unconnected-(XIO-Pad5)") (class "Default")
      (node (ref "XIO") (pin "5") (pinfunction "5_5") (pintype "passive"))
    )
    (net (code "122") (name "unconnected-(XIO-Pad6)") (class "Default")
      (node (ref "XIO") (pin "6") (pinfunction "6_6") (pintype "passive"))
    )
    (net (code "123") (name "unconnected-(XIO-Pad7)") (class "Default")
      (node (ref "XIO") (pin "7") (pinfunction "7_7") (pintype "passive"))
    )
    (net (code "124") (name "unconnected-(XIO-Pad8)") (class "Default")
      (node (ref "XIO") (pin "8") (pinfunction "8_8") (pintype "passive"))
    )
    (net (code "125") (name "unconnected-(XIO-Pad9)") (class "Default")
      (node (ref "XIO") (pin "9") (pinfunction "9_9") (pintype "passive"))
    )
    (net (code "126") (name "unconnected-(XIO-Pad10)") (class "Default")
      (node (ref "XIO") (pin "10") (pinfunction "10_10") (pintype "passive"))
    )
    (net (code "127") (name "unconnected-(XIO-Pad11)") (class "Default")
      (node (ref "XIO") (pin "11") (pinfunction "11_11") (pintype "passive"))
    )
    (net (code "128") (name "unconnected-(XIO-Pad13)") (class "Default")
      (node (ref "XIO") (pin "13") (pinfunction "13_13") (pintype "passive"))
    )
    (net (code "129") (name "unconnected-(XIO-Pad15)") (class "Default")
      (node (ref "XIO") (pin "15") (pinfunction "15_15") (pintype "passive"))
    )
    (net (code "130") (name "unconnected-(XIO-Pad17)") (class "Default")
      (node (ref "XIO") (pin "17") (pinfunction "17_17") (pintype "passive"))
    )
    (net (code "131") (name "unconnected-(XIO-Pad19)") (class "Default")
      (node (ref "XIO") (pin "19") (pinfunction "19_19") (pintype "passive"))
    )
    (net (code "132") (name "unconnected-(XIO-Pad21)") (class "Default")
      (node (ref "XIO") (pin "21") (pinfunction "21_21") (pintype "passive"))
    )
    (net (code "133") (name "unconnected-(XIO-Pad23)") (class "Default")
      (node (ref "XIO") (pin "23") (pinfunction "23_23") (pintype "passive"))
    )
    (net (code "134") (name "unconnected-(XIO-Pad25)") (class "Default")
      (node (ref "XIO") (pin "25") (pinfunction "25_25") (pintype "passive"))
    )
    (net (code "135") (name "unconnected-(XIO-Pad27)") (class "Default")
      (node (ref "XIO") (pin "27") (pinfunction "27_27") (pintype "passive"))
    )
    (net (code "136") (name "unconnected-(XIO-Pad29)") (class "Default")
      (node (ref "XIO") (pin "29") (pinfunction "29_29") (pintype "passive"))
    )
  )
)
